# R201C.net
KiCad netlist of a schematic drawn in EAGLE
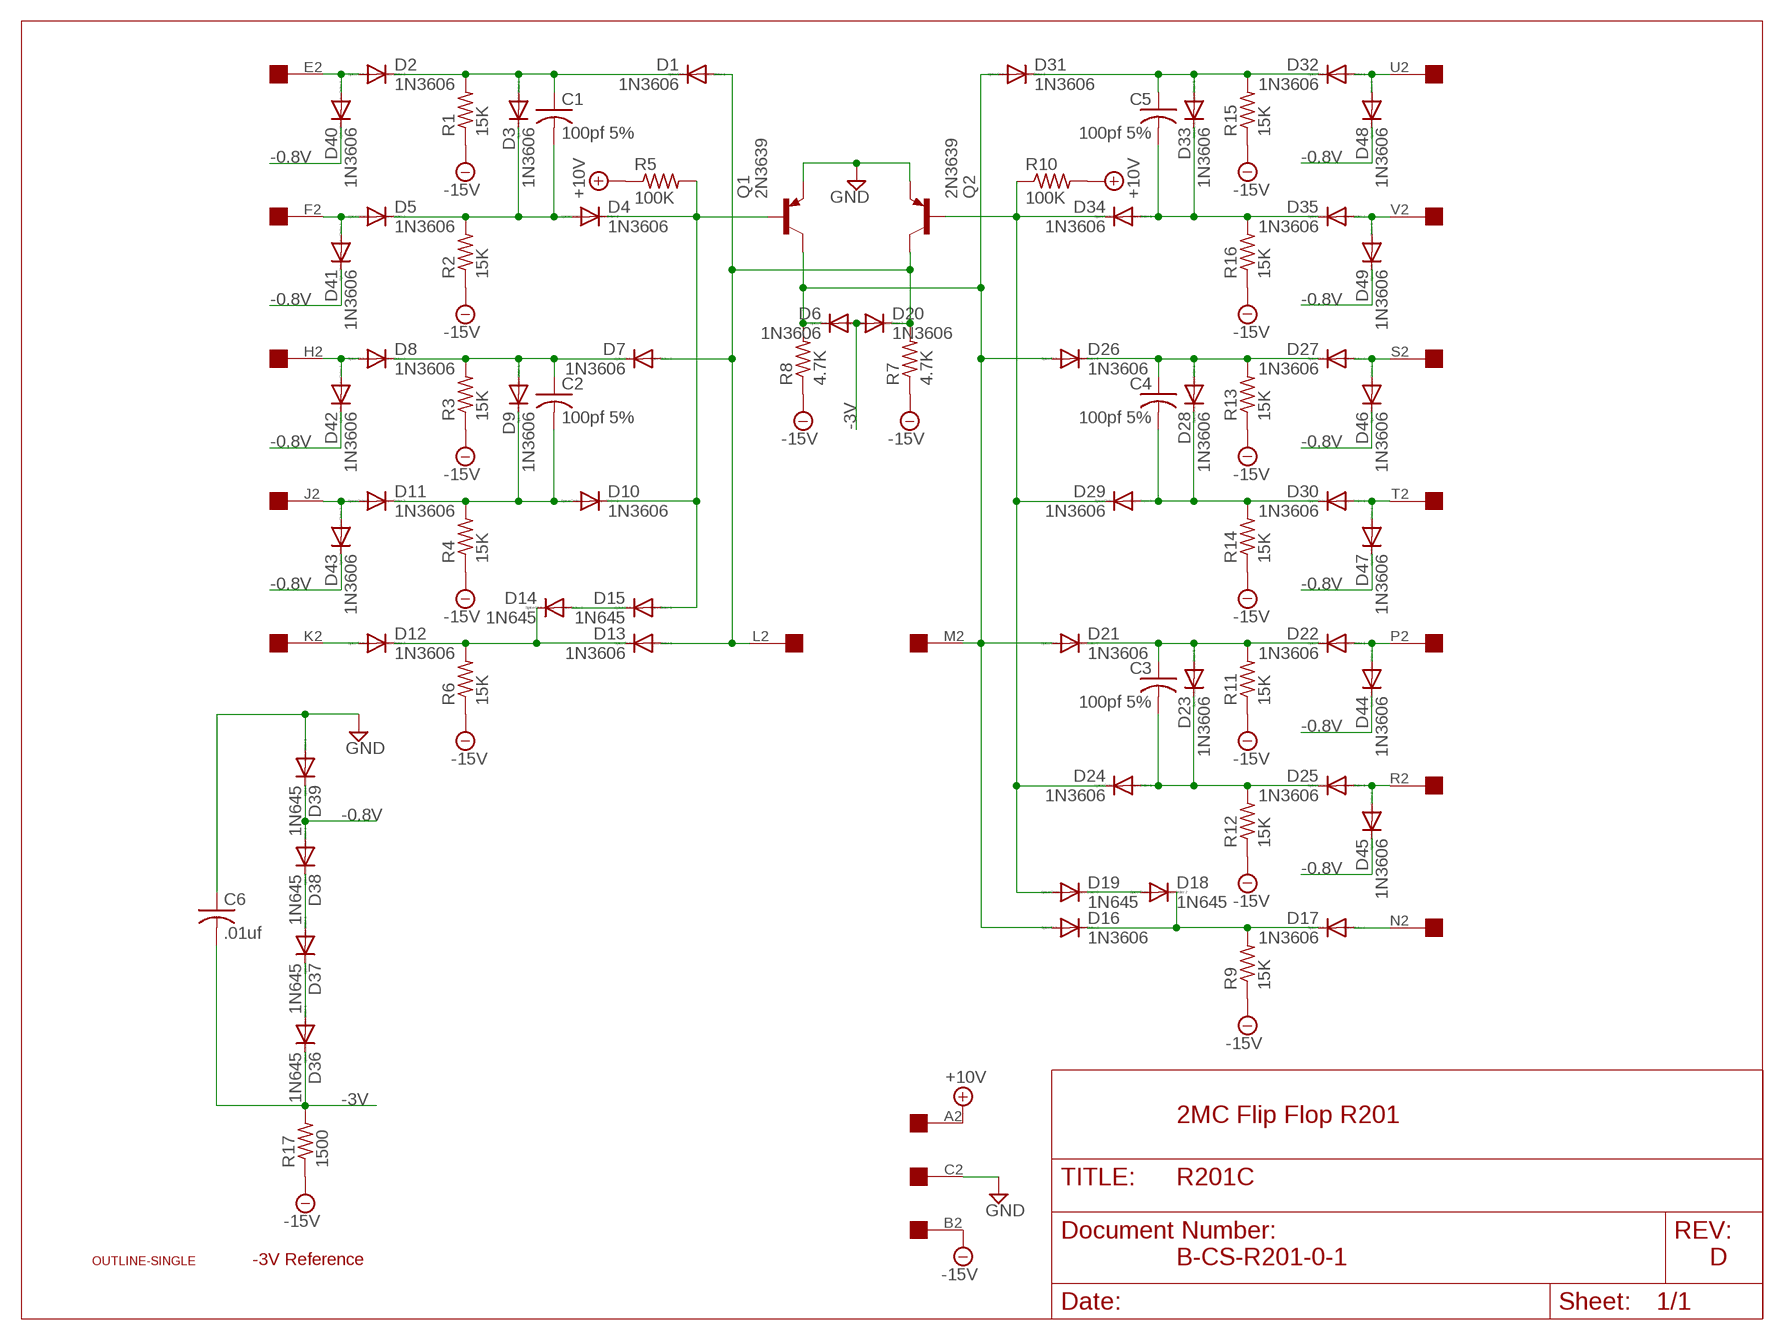
[diagram p0: schematic, sheet 1]

(export (version "E")
  (design (tool "Eeschema 10.0.6"))
  (components
    (comp (ref "C1")
      (value "100pf 5%")
      (footprint "eagle-import:C050-025X075")
      (libsource (lib "eagle-import") (part "C-US050-025X075"))
    )
    (comp (ref "C2")
      (value "100pf 5%")
      (footprint "eagle-import:C050-025X075")
      (libsource (lib "eagle-import") (part "C-US050-025X075"))
    )
    (comp (ref "C3")
      (value "100pf 5%")
      (footprint "eagle-import:C050-025X075")
      (libsource (lib "eagle-import") (part "C-US050-025X075"))
    )
    (comp (ref "C4")
      (value "100pf 5%")
      (footprint "eagle-import:C050-025X075")
      (libsource (lib "eagle-import") (part "C-US050-025X075"))
    )
    (comp (ref "C5")
      (value "100pf 5%")
      (footprint "eagle-import:C050-025X075")
      (libsource (lib "eagle-import") (part "C-US050-025X075"))
    )
    (comp (ref "C6")
      (value ".01uf")
      (footprint "eagle-import:C050-025X075")
      (libsource (lib "eagle-import") (part "C-US050-025X075"))
    )
    (comp (ref "D1")
      (value "1N3606")
      (footprint "eagle-import:DO35-10")
      (libsource (lib "eagle-import") (part "1N4148DO35-10"))
    )
    (comp (ref "D2")
      (value "1N3606")
      (footprint "eagle-import:DO35-10")
      (libsource (lib "eagle-import") (part "1N4148DO35-10"))
    )
    (comp (ref "D3")
      (value "1N3606")
      (footprint "eagle-import:DO35-10")
      (libsource (lib "eagle-import") (part "1N4148DO35-10"))
    )
    (comp (ref "D4")
      (value "1N3606")
      (footprint "eagle-import:DO35-10")
      (libsource (lib "eagle-import") (part "1N4148DO35-10"))
    )
    (comp (ref "D5")
      (value "1N3606")
      (footprint "eagle-import:DO35-10")
      (libsource (lib "eagle-import") (part "1N4148DO35-10"))
    )
    (comp (ref "D6")
      (value "1N3606")
      (footprint "eagle-import:DO35-10")
      (libsource (lib "eagle-import") (part "1N4148DO35-10"))
    )
    (comp (ref "D7")
      (value "1N3606")
      (footprint "eagle-import:DO35-10")
      (libsource (lib "eagle-import") (part "1N4148DO35-10"))
    )
    (comp (ref "D8")
      (value "1N3606")
      (footprint "eagle-import:DO35-10")
      (libsource (lib "eagle-import") (part "1N4148DO35-10"))
    )
    (comp (ref "D9")
      (value "1N3606")
      (footprint "eagle-import:DO35-10")
      (libsource (lib "eagle-import") (part "1N4148DO35-10"))
    )
    (comp (ref "D10")
      (value "1N3606")
      (footprint "eagle-import:DO35-10")
      (libsource (lib "eagle-import") (part "1N4148DO35-10"))
    )
    (comp (ref "D11")
      (value "1N3606")
      (footprint "eagle-import:DO35-10")
      (libsource (lib "eagle-import") (part "1N4148DO35-10"))
    )
    (comp (ref "D12")
      (value "1N3606")
      (footprint "eagle-import:DO35-10")
      (libsource (lib "eagle-import") (part "1N4148DO35-10"))
    )
    (comp (ref "D13")
      (value "1N3606")
      (footprint "eagle-import:DO35-10")
      (libsource (lib "eagle-import") (part "1N4148DO35-10"))
    )
    (comp (ref "D14")
      (value "1N645")
      (footprint "eagle-import:DO35-10")
      (libsource (lib "eagle-import") (part "1N4148DO35-10"))
    )
    (comp (ref "D15")
      (value "1N645")
      (footprint "eagle-import:DO35-10")
      (libsource (lib "eagle-import") (part "1N4148DO35-10"))
    )
    (comp (ref "D16")
      (value "1N3606")
      (footprint "eagle-import:DO35-10")
      (libsource (lib "eagle-import") (part "1N4148DO35-10"))
    )
    (comp (ref "D17")
      (value "1N3606")
      (footprint "eagle-import:DO35-10")
      (libsource (lib "eagle-import") (part "1N4148DO35-10"))
    )
    (comp (ref "D18")
      (value "1N645")
      (footprint "eagle-import:DO35-10")
      (libsource (lib "eagle-import") (part "1N4148DO35-10"))
    )
    (comp (ref "D19")
      (value "1N645")
      (footprint "eagle-import:DO35-10")
      (libsource (lib "eagle-import") (part "1N4148DO35-10"))
    )
    (comp (ref "D20")
      (value "1N3606")
      (footprint "eagle-import:DO35-10")
      (libsource (lib "eagle-import") (part "1N4148DO35-10"))
    )
    (comp (ref "D21")
      (value "1N3606")
      (footprint "eagle-import:DO35-10")
      (libsource (lib "eagle-import") (part "1N4148DO35-10"))
    )
    (comp (ref "D22")
      (value "1N3606")
      (footprint "eagle-import:DO35-10")
      (libsource (lib "eagle-import") (part "1N4148DO35-10"))
    )
    (comp (ref "D23")
      (value "1N3606")
      (footprint "eagle-import:DO35-10")
      (libsource (lib "eagle-import") (part "1N4148DO35-10"))
    )
    (comp (ref "D24")
      (value "1N3606")
      (footprint "eagle-import:DO35-10")
      (libsource (lib "eagle-import") (part "1N4148DO35-10"))
    )
    (comp (ref "D25")
      (value "1N3606")
      (footprint "eagle-import:DO35-10")
      (libsource (lib "eagle-import") (part "1N4148DO35-10"))
    )
    (comp (ref "D26")
      (value "1N3606")
      (footprint "eagle-import:DO35-10")
      (libsource (lib "eagle-import") (part "1N4148DO35-10"))
    )
    (comp (ref "D27")
      (value "1N3606")
      (footprint "eagle-import:DO35-10")
      (libsource (lib "eagle-import") (part "1N4148DO35-10"))
    )
    (comp (ref "D28")
      (value "1N3606")
      (footprint "eagle-import:DO35-10")
      (libsource (lib "eagle-import") (part "1N4148DO35-10"))
    )
    (comp (ref "D29")
      (value "1N3606")
      (footprint "eagle-import:DO35-10")
      (libsource (lib "eagle-import") (part "1N4148DO35-10"))
    )
    (comp (ref "D30")
      (value "1N3606")
      (footprint "eagle-import:DO35-10")
      (libsource (lib "eagle-import") (part "1N4148DO35-10"))
    )
    (comp (ref "D31")
      (value "1N3606")
      (footprint "eagle-import:DO35-10")
      (libsource (lib "eagle-import") (part "1N4148DO35-10"))
    )
    (comp (ref "D32")
      (value "1N3606")
      (footprint "eagle-import:DO35-10")
      (libsource (lib "eagle-import") (part "1N4148DO35-10"))
    )
    (comp (ref "D33")
      (value "1N3606")
      (footprint "eagle-import:DO35-10")
      (libsource (lib "eagle-import") (part "1N4148DO35-10"))
    )
    (comp (ref "D34")
      (value "1N3606")
      (footprint "eagle-import:DO35-10")
      (libsource (lib "eagle-import") (part "1N4148DO35-10"))
    )
    (comp (ref "D35")
      (value "1N3606")
      (footprint "eagle-import:DO35-10")
      (libsource (lib "eagle-import") (part "1N4148DO35-10"))
    )
    (comp (ref "D36")
      (value "1N645")
      (footprint "eagle-import:DO35-10")
      (libsource (lib "eagle-import") (part "1N4148DO35-10"))
    )
    (comp (ref "D37")
      (value "1N645")
      (footprint "eagle-import:DO35-10")
      (libsource (lib "eagle-import") (part "1N4148DO35-10"))
    )
    (comp (ref "D38")
      (value "1N645")
      (footprint "eagle-import:DO35-10")
      (libsource (lib "eagle-import") (part "1N4148DO35-10"))
    )
    (comp (ref "D39")
      (value "1N645")
      (footprint "eagle-import:DO35-10")
      (libsource (lib "eagle-import") (part "1N4148DO35-10"))
    )
    (comp (ref "D40")
      (value "1N3606")
      (footprint "eagle-import:DO35-10")
      (libsource (lib "eagle-import") (part "1N4148DO35-10"))
    )
    (comp (ref "D41")
      (value "1N3606")
      (footprint "eagle-import:DO35-10")
      (libsource (lib "eagle-import") (part "1N4148DO35-10"))
    )
    (comp (ref "D42")
      (value "1N3606")
      (footprint "eagle-import:DO35-10")
      (libsource (lib "eagle-import") (part "1N4148DO35-10"))
    )
    (comp (ref "D43")
      (value "1N3606")
      (footprint "eagle-import:DO35-10")
      (libsource (lib "eagle-import") (part "1N4148DO35-10"))
    )
    (comp (ref "D44")
      (value "1N3606")
      (footprint "eagle-import:DO35-10")
      (libsource (lib "eagle-import") (part "1N4148DO35-10"))
    )
    (comp (ref "D45")
      (value "1N3606")
      (footprint "eagle-import:DO35-10")
      (libsource (lib "eagle-import") (part "1N4148DO35-10"))
    )
    (comp (ref "D46")
      (value "1N3606")
      (footprint "eagle-import:DO35-10")
      (libsource (lib "eagle-import") (part "1N4148DO35-10"))
    )
    (comp (ref "D47")
      (value "1N3606")
      (footprint "eagle-import:DO35-10")
      (libsource (lib "eagle-import") (part "1N4148DO35-10"))
    )
    (comp (ref "D48")
      (value "1N3606")
      (footprint "eagle-import:DO35-10")
      (libsource (lib "eagle-import") (part "1N4148DO35-10"))
    )
    (comp (ref "D49")
      (value "1N3606")
      (footprint "eagle-import:DO35-10")
      (libsource (lib "eagle-import") (part "1N4148DO35-10"))
    )
    (comp (ref "Q1")
      (value "2N3639")
      (footprint "eagle-import:TO39")
      (libsource (lib "eagle-import") (part "2N3637"))
    )
    (comp (ref "Q2")
      (value "2N3639")
      (footprint "eagle-import:TO39")
      (libsource (lib "eagle-import") (part "2N3637"))
    )
    (comp (ref "R1")
      (value "15K")
      (footprint "eagle-import:0207_10")
      (libsource (lib "eagle-import") (part "R-US_0207/10"))
    )
    (comp (ref "R2")
      (value "15K")
      (footprint "eagle-import:0207_10")
      (libsource (lib "eagle-import") (part "R-US_0207/10"))
    )
    (comp (ref "R3")
      (value "15K")
      (footprint "eagle-import:0207_10")
      (libsource (lib "eagle-import") (part "R-US_0207/10"))
    )
    (comp (ref "R4")
      (value "15K")
      (footprint "eagle-import:0207_10")
      (libsource (lib "eagle-import") (part "R-US_0207/10"))
    )
    (comp (ref "R5")
      (value "100K")
      (footprint "eagle-import:0207_10")
      (libsource (lib "eagle-import") (part "R-US_0207/10"))
    )
    (comp (ref "R6")
      (value "15K")
      (footprint "eagle-import:0207_10")
      (libsource (lib "eagle-import") (part "R-US_0207/10"))
    )
    (comp (ref "R7")
      (value "4.7K")
      (footprint "eagle-import:0207_10")
      (libsource (lib "eagle-import") (part "R-US_0207/10"))
    )
    (comp (ref "R8")
      (value "4.7K")
      (footprint "eagle-import:0207_10")
      (libsource (lib "eagle-import") (part "R-US_0207/10"))
    )
    (comp (ref "R9")
      (value "15K")
      (footprint "eagle-import:0207_10")
      (libsource (lib "eagle-import") (part "R-US_0207/10"))
    )
    (comp (ref "R10")
      (value "100K")
      (footprint "eagle-import:0207_10")
      (libsource (lib "eagle-import") (part "R-US_0207/10"))
    )
    (comp (ref "R11")
      (value "15K")
      (footprint "eagle-import:0207_10")
      (libsource (lib "eagle-import") (part "R-US_0207/10"))
    )
    (comp (ref "R12")
      (value "15K")
      (footprint "eagle-import:0207_10")
      (libsource (lib "eagle-import") (part "R-US_0207/10"))
    )
    (comp (ref "R13")
      (value "15K")
      (footprint "eagle-import:0207_10")
      (libsource (lib "eagle-import") (part "R-US_0207/10"))
    )
    (comp (ref "R14")
      (value "15K")
      (footprint "eagle-import:0207_10")
      (libsource (lib "eagle-import") (part "R-US_0207/10"))
    )
    (comp (ref "R15")
      (value "15K")
      (footprint "eagle-import:0207_10")
      (libsource (lib "eagle-import") (part "R-US_0207/10"))
    )
    (comp (ref "R16")
      (value "15K")
      (footprint "eagle-import:0207_10")
      (libsource (lib "eagle-import") (part "R-US_0207/10"))
    )
    (comp (ref "R17")
      (value "1500")
      (footprint "eagle-import:0207_10")
      (libsource (lib "eagle-import") (part "R-US_0207/10"))
    )
    (comp (ref "U$1")
      (value "OUTLINE-SINGLE")
      (footprint "eagle-import:SINGLE")
      (libsource (lib "eagle-import") (part "OUTLINE-SINGLE"))
    )
    (comp (ref "U$2")
      (value "EDGE-1")
      (footprint "eagle-import:EDGE-CON1")
      (libsource (lib "eagle-import") (part "EDGE-1"))
    )
  )
  (nets
    (net (code "1") (name "+10V") (class "Default")
      (node (ref "R10") (pin "2") (pinfunction "2_2") (pintype "passive"))
      (node (ref "R5") (pin "1") (pinfunction "1_1") (pintype "passive"))
      (node (ref "U$2") (pin "A2") (pinfunction "1_A2") (pintype "bidirectional"))
    )
    (net (code "2") (name "-15V") (class "Default")
      (node (ref "R1") (pin "1") (pinfunction "1_1") (pintype "passive"))
      (node (ref "R11") (pin "1") (pinfunction "1_1") (pintype "passive"))
      (node (ref "R12") (pin "1") (pinfunction "1_1") (pintype "passive"))
      (node (ref "R13") (pin "1") (pinfunction "1_1") (pintype "passive"))
      (node (ref "R14") (pin "1") (pinfunction "1_1") (pintype "passive"))
      (node (ref "R15") (pin "1") (pinfunction "1_1") (pintype "passive"))
      (node (ref "R16") (pin "1") (pinfunction "1_1") (pintype "passive"))
      (node (ref "R17") (pin "1") (pinfunction "1_1") (pintype "passive"))
      (node (ref "R2") (pin "1") (pinfunction "1_1") (pintype "passive"))
      (node (ref "R3") (pin "1") (pinfunction "1_1") (pintype "passive"))
      (node (ref "R4") (pin "1") (pinfunction "1_1") (pintype "passive"))
      (node (ref "R6") (pin "1") (pinfunction "1_1") (pintype "passive"))
      (node (ref "R7") (pin "1") (pinfunction "1_1") (pintype "passive"))
      (node (ref "R8") (pin "1") (pinfunction "1_1") (pintype "passive"))
      (node (ref "R9") (pin "1") (pinfunction "1_1") (pintype "passive"))
      (node (ref "U$2") (pin "B2") (pinfunction "1_B2") (pintype "bidirectional"))
    )
    (net (code "3") (name "/-0.8V") (class "Default")
      (node (ref "D38") (pin "A") (pinfunction "A_A") (pintype "passive"))
      (node (ref "D39") (pin "C") (pinfunction "C_C") (pintype "passive"))
      (node (ref "D40") (pin "C") (pinfunction "C_C") (pintype "passive"))
      (node (ref "D41") (pin "C") (pinfunction "C_C") (pintype "passive"))
      (node (ref "D42") (pin "C") (pinfunction "C_C") (pintype "passive"))
      (node (ref "D43") (pin "C") (pinfunction "C_C") (pintype "passive"))
      (node (ref "D44") (pin "C") (pinfunction "C_C") (pintype "passive"))
      (node (ref "D45") (pin "C") (pinfunction "C_C") (pintype "passive"))
      (node (ref "D46") (pin "C") (pinfunction "C_C") (pintype "passive"))
      (node (ref "D47") (pin "C") (pinfunction "C_C") (pintype "passive"))
      (node (ref "D48") (pin "C") (pinfunction "C_C") (pintype "passive"))
      (node (ref "D49") (pin "C") (pinfunction "C_C") (pintype "passive"))
    )
    (net (code "4") (name "/-3V") (class "Default")
      (node (ref "C6") (pin "2") (pinfunction "2_2") (pintype "passive"))
      (node (ref "D20") (pin "A") (pinfunction "A_A") (pintype "passive"))
      (node (ref "D36") (pin "C") (pinfunction "C_C") (pintype "passive"))
      (node (ref "D6") (pin "A") (pinfunction "A_A") (pintype "passive"))
      (node (ref "R17") (pin "2") (pinfunction "2_2") (pintype "passive"))
    )
    (net (code "5") (name "GND") (class "Default")
      (node (ref "C6") (pin "1") (pinfunction "1_1") (pintype "passive"))
      (node (ref "D39") (pin "A") (pinfunction "A_A") (pintype "passive"))
      (node (ref "Q1") (pin "1") (pinfunction "E_1") (pintype "passive"))
      (node (ref "Q2") (pin "1") (pinfunction "E_1") (pintype "passive"))
      (node (ref "U$2") (pin "C2") (pinfunction "1_C2") (pintype "bidirectional"))
    )
    (net (code "6") (name "Net-(C1-Pad1)") (class "Default")
      (node (ref "C1") (pin "1") (pinfunction "1_1") (pintype "passive"))
      (node (ref "D1") (pin "C") (pinfunction "C_C") (pintype "passive"))
      (node (ref "D2") (pin "C") (pinfunction "C_C") (pintype "passive"))
      (node (ref "D3") (pin "A") (pinfunction "A_A") (pintype "passive"))
      (node (ref "R1") (pin "2") (pinfunction "2_2") (pintype "passive"))
    )
    (net (code "7") (name "Net-(C1-Pad2)") (class "Default")
      (node (ref "C1") (pin "2") (pinfunction "2_2") (pintype "passive"))
      (node (ref "D3") (pin "C") (pinfunction "C_C") (pintype "passive"))
      (node (ref "D4") (pin "A") (pinfunction "A_A") (pintype "passive"))
      (node (ref "D5") (pin "C") (pinfunction "C_C") (pintype "passive"))
      (node (ref "R2") (pin "2") (pinfunction "2_2") (pintype "passive"))
    )
    (net (code "8") (name "Net-(C2-Pad1)") (class "Default")
      (node (ref "C2") (pin "1") (pinfunction "1_1") (pintype "passive"))
      (node (ref "D7") (pin "C") (pinfunction "C_C") (pintype "passive"))
      (node (ref "D8") (pin "C") (pinfunction "C_C") (pintype "passive"))
      (node (ref "D9") (pin "A") (pinfunction "A_A") (pintype "passive"))
      (node (ref "R3") (pin "2") (pinfunction "2_2") (pintype "passive"))
    )
    (net (code "9") (name "Net-(C2-Pad2)") (class "Default")
      (node (ref "C2") (pin "2") (pinfunction "2_2") (pintype "passive"))
      (node (ref "D10") (pin "A") (pinfunction "A_A") (pintype "passive"))
      (node (ref "D11") (pin "C") (pinfunction "C_C") (pintype "passive"))
      (node (ref "D9") (pin "C") (pinfunction "C_C") (pintype "passive"))
      (node (ref "R4") (pin "2") (pinfunction "2_2") (pintype "passive"))
    )
    (net (code "10") (name "Net-(C3-Pad1)") (class "Default")
      (node (ref "C3") (pin "1") (pinfunction "1_1") (pintype "passive"))
      (node (ref "D21") (pin "C") (pinfunction "C_C") (pintype "passive"))
      (node (ref "D22") (pin "C") (pinfunction "C_C") (pintype "passive"))
      (node (ref "D23") (pin "A") (pinfunction "A_A") (pintype "passive"))
      (node (ref "R11") (pin "2") (pinfunction "2_2") (pintype "passive"))
    )
    (net (code "11") (name "Net-(C3-Pad2)") (class "Default")
      (node (ref "C3") (pin "2") (pinfunction "2_2") (pintype "passive"))
      (node (ref "D23") (pin "C") (pinfunction "C_C") (pintype "passive"))
      (node (ref "D24") (pin "A") (pinfunction "A_A") (pintype "passive"))
      (node (ref "D25") (pin "C") (pinfunction "C_C") (pintype "passive"))
      (node (ref "R12") (pin "2") (pinfunction "2_2") (pintype "passive"))
    )
    (net (code "12") (name "Net-(C4-Pad1)") (class "Default")
      (node (ref "C4") (pin "1") (pinfunction "1_1") (pintype "passive"))
      (node (ref "D26") (pin "C") (pinfunction "C_C") (pintype "passive"))
      (node (ref "D27") (pin "C") (pinfunction "C_C") (pintype "passive"))
      (node (ref "D28") (pin "A") (pinfunction "A_A") (pintype "passive"))
      (node (ref "R13") (pin "2") (pinfunction "2_2") (pintype "passive"))
    )
    (net (code "13") (name "Net-(C4-Pad2)") (class "Default")
      (node (ref "C4") (pin "2") (pinfunction "2_2") (pintype "passive"))
      (node (ref "D28") (pin "C") (pinfunction "C_C") (pintype "passive"))
      (node (ref "D29") (pin "A") (pinfunction "A_A") (pintype "passive"))
      (node (ref "D30") (pin "C") (pinfunction "C_C") (pintype "passive"))
      (node (ref "R14") (pin "2") (pinfunction "2_2") (pintype "passive"))
    )
    (net (code "14") (name "Net-(C5-Pad1)") (class "Default")
      (node (ref "C5") (pin "1") (pinfunction "1_1") (pintype "passive"))
      (node (ref "D31") (pin "C") (pinfunction "C_C") (pintype "passive"))
      (node (ref "D32") (pin "C") (pinfunction "C_C") (pintype "passive"))
      (node (ref "D33") (pin "A") (pinfunction "A_A") (pintype "passive"))
      (node (ref "R15") (pin "2") (pinfunction "2_2") (pintype "passive"))
    )
    (net (code "15") (name "Net-(C5-Pad2)") (class "Default")
      (node (ref "C5") (pin "2") (pinfunction "2_2") (pintype "passive"))
      (node (ref "D33") (pin "C") (pinfunction "C_C") (pintype "passive"))
      (node (ref "D34") (pin "A") (pinfunction "A_A") (pintype "passive"))
      (node (ref "D35") (pin "C") (pinfunction "C_C") (pintype "passive"))
      (node (ref "R16") (pin "2") (pinfunction "2_2") (pintype "passive"))
    )
    (net (code "16") (name "Net-(D12-PadC)") (class "Default")
      (node (ref "D12") (pin "C") (pinfunction "C_C") (pintype "passive"))
      (node (ref "D13") (pin "C") (pinfunction "C_C") (pintype "passive"))
      (node (ref "D14") (pin "C") (pinfunction "C_C") (pintype "passive"))
      (node (ref "R6") (pin "2") (pinfunction "2_2") (pintype "passive"))
    )
    (net (code "17") (name "Net-(D14-PadA)") (class "Default")
      (node (ref "D14") (pin "A") (pinfunction "A_A") (pintype "passive"))
      (node (ref "D15") (pin "C") (pinfunction "C_C") (pintype "passive"))
    )
    (net (code "18") (name "Net-(D16-PadC)") (class "Default")
      (node (ref "D16") (pin "C") (pinfunction "C_C") (pintype "passive"))
      (node (ref "D17") (pin "C") (pinfunction "C_C") (pintype "passive"))
      (node (ref "D18") (pin "C") (pinfunction "C_C") (pintype "passive"))
      (node (ref "R9") (pin "2") (pinfunction "2_2") (pintype "passive"))
    )
    (net (code "19") (name "Net-(D18-PadA)") (class "Default")
      (node (ref "D18") (pin "A") (pinfunction "A_A") (pintype "passive"))
      (node (ref "D19") (pin "C") (pinfunction "C_C") (pintype "passive"))
    )
    (net (code "20") (name "Net-(D36-PadA)") (class "Default")
      (node (ref "D36") (pin "A") (pinfunction "A_A") (pintype "passive"))
      (node (ref "D37") (pin "C") (pinfunction "C_C") (pintype "passive"))
    )
    (net (code "21") (name "Net-(D37-PadA)") (class "Default")
      (node (ref "D37") (pin "A") (pinfunction "A_A") (pintype "passive"))
      (node (ref "D38") (pin "C") (pinfunction "C_C") (pintype "passive"))
    )
    (net (code "22") (name "Net-(Q1-B)") (class "Default")
      (node (ref "D10") (pin "C") (pinfunction "C_C") (pintype "passive"))
      (node (ref "D15") (pin "A") (pinfunction "A_A") (pintype "passive"))
      (node (ref "D4") (pin "C") (pinfunction "C_C") (pintype "passive"))
      (node (ref "Q1") (pin "2") (pinfunction "B_2") (pintype "passive"))
      (node (ref "R5") (pin "2") (pinfunction "2_2") (pintype "passive"))
    )
    (net (code "23") (name "Net-(Q1-C)") (class "Default")
      (node (ref "D16") (pin "A") (pinfunction "A_A") (pintype "passive"))
      (node (ref "D21") (pin "A") (pinfunction "A_A") (pintype "passive"))
      (node (ref "D26") (pin "A") (pinfunction "A_A") (pintype "passive"))
      (node (ref "D31") (pin "A") (pinfunction "A_A") (pintype "passive"))
      (node (ref "D6") (pin "C") (pinfunction "C_C") (pintype "passive"))
      (node (ref "Q1") (pin "3") (pinfunction "C_3") (pintype "passive"))
      (node (ref "R8") (pin "2") (pinfunction "2_2") (pintype "passive"))
      (node (ref "U$2") (pin "M2") (pinfunction "1_M2") (pintype "bidirectional"))
    )
    (net (code "24") (name "Net-(Q2-B)") (class "Default")
      (node (ref "D19") (pin "A") (pinfunction "A_A") (pintype "passive"))
      (node (ref "D24") (pin "C") (pinfunction "C_C") (pintype "passive"))
      (node (ref "D29") (pin "C") (pinfunction "C_C") (pintype "passive"))
      (node (ref "D34") (pin "C") (pinfunction "C_C") (pintype "passive"))
      (node (ref "Q2") (pin "2") (pinfunction "B_2") (pintype "passive"))
      (node (ref "R10") (pin "1") (pinfunction "1_1") (pintype "passive"))
    )
    (net (code "25") (name "Net-(Q2-C)") (class "Default")
      (node (ref "D1") (pin "A") (pinfunction "A_A") (pintype "passive"))
      (node (ref "D13") (pin "A") (pinfunction "A_A") (pintype "passive"))
      (node (ref "D20") (pin "C") (pinfunction "C_C") (pintype "passive"))
      (node (ref "D7") (pin "A") (pinfunction "A_A") (pintype "passive"))
      (node (ref "Q2") (pin "3") (pinfunction "C_3") (pintype "passive"))
      (node (ref "R7") (pin "2") (pinfunction "2_2") (pintype "passive"))
      (node (ref "U$2") (pin "L2") (pinfunction "1_L2") (pintype "bidirectional"))
    )
    (net (code "26") (name "Net-(U$2E-1)") (class "Default")
      (node (ref "D2") (pin "A") (pinfunction "A_A") (pintype "passive"))
      (node (ref "D40") (pin "A") (pinfunction "A_A") (pintype "passive"))
      (node (ref "U$2") (pin "E2") (pinfunction "1_E2") (pintype "bidirectional"))
    )
    (net (code "27") (name "Net-(U$2F-1)") (class "Default")
      (node (ref "D41") (pin "A") (pinfunction "A_A") (pintype "passive"))
      (node (ref "D5") (pin "A") (pinfunction "A_A") (pintype "passive"))
      (node (ref "U$2") (pin "F2") (pinfunction "1_F2") (pintype "bidirectional"))
    )
    (net (code "28") (name "Net-(U$2G-1)") (class "Default")
      (node (ref "D42") (pin "A") (pinfunction "A_A") (pintype "passive"))
      (node (ref "D8") (pin "A") (pinfunction "A_A") (pintype "passive"))
      (node (ref "U$2") (pin "H2") (pinfunction "1_H2") (pintype "bidirectional"))
    )
    (net (code "29") (name "Net-(U$2H-1)") (class "Default")
      (node (ref "D11") (pin "A") (pinfunction "A_A") (pintype "passive"))
      (node (ref "D43") (pin "A") (pinfunction "A_A") (pintype "passive"))
      (node (ref "U$2") (pin "J2") (pinfunction "1_J2") (pintype "bidirectional"))
    )
    (net (code "30") (name "Net-(U$2I-1)") (class "Default")
      (node (ref "D12") (pin "A") (pinfunction "A_A") (pintype "passive"))
      (node (ref "U$2") (pin "K2") (pinfunction "1_K2") (pintype "bidirectional"))
    )
    (net (code "31") (name "Net-(U$2L-1)") (class "Default")
      (node (ref "D17") (pin "A") (pinfunction "A_A") (pintype "passive"))
      (node (ref "U$2") (pin "N2") (pinfunction "1_N2") (pintype "bidirectional"))
    )
    (net (code "32") (name "Net-(U$2M-1)") (class "Default")
      (node (ref "D22") (pin "A") (pinfunction "A_A") (pintype "passive"))
      (node (ref "D44") (pin "A") (pinfunction "A_A") (pintype "passive"))
      (node (ref "U$2") (pin "P2") (pinfunction "1_P2") (pintype "bidirectional"))
    )
    (net (code "33") (name "Net-(U$2N-1)") (class "Default")
      (node (ref "D25") (pin "A") (pinfunction "A_A") (pintype "passive"))
      (node (ref "D45") (pin "A") (pinfunction "A_A") (pintype "passive"))
      (node (ref "U$2") (pin "R2") (pinfunction "1_R2") (pintype "bidirectional"))
    )
    (net (code "34") (name "Net-(U$2O-1)") (class "Default")
      (node (ref "D27") (pin "A") (pinfunction "A_A") (pintype "passive"))
      (node (ref "D46") (pin "A") (pinfunction "A_A") (pintype "passive"))
      (node (ref "U$2") (pin "S2") (pinfunction "1_S2") (pintype "bidirectional"))
    )
    (net (code "35") (name "Net-(U$2P-1)") (class "Default")
      (node (ref "D30") (pin "A") (pinfunction "A_A") (pintype "passive"))
      (node (ref "D47") (pin "A") (pinfunction "A_A") (pintype "passive"))
      (node (ref "U$2") (pin "T2") (pinfunction "1_T2") (pintype "bidirectional"))
    )
    (net (code "36") (name "Net-(U$2Q-1)") (class "Default")
      (node (ref "D32") (pin "A") (pinfunction "A_A") (pintype "passive"))
      (node (ref "D48") (pin "A") (pinfunction "A_A") (pintype "passive"))
      (node (ref "U$2") (pin "U2") (pinfunction "1_U2") (pintype "bidirectional"))
    )
    (net (code "37") (name "Net-(U$2R-1)") (class "Default")
      (node (ref "D35") (pin "A") (pinfunction "A_A") (pintype "passive"))
      (node (ref "D49") (pin "A") (pinfunction "A_A") (pintype "passive"))
      (node (ref "U$2") (pin "V2") (pinfunction "1_V2") (pintype "bidirectional"))
    )
  )
)
